# Arduino_Uno_v1_schematic.net
KiCad netlist of a schematic drawn in Altium Designer
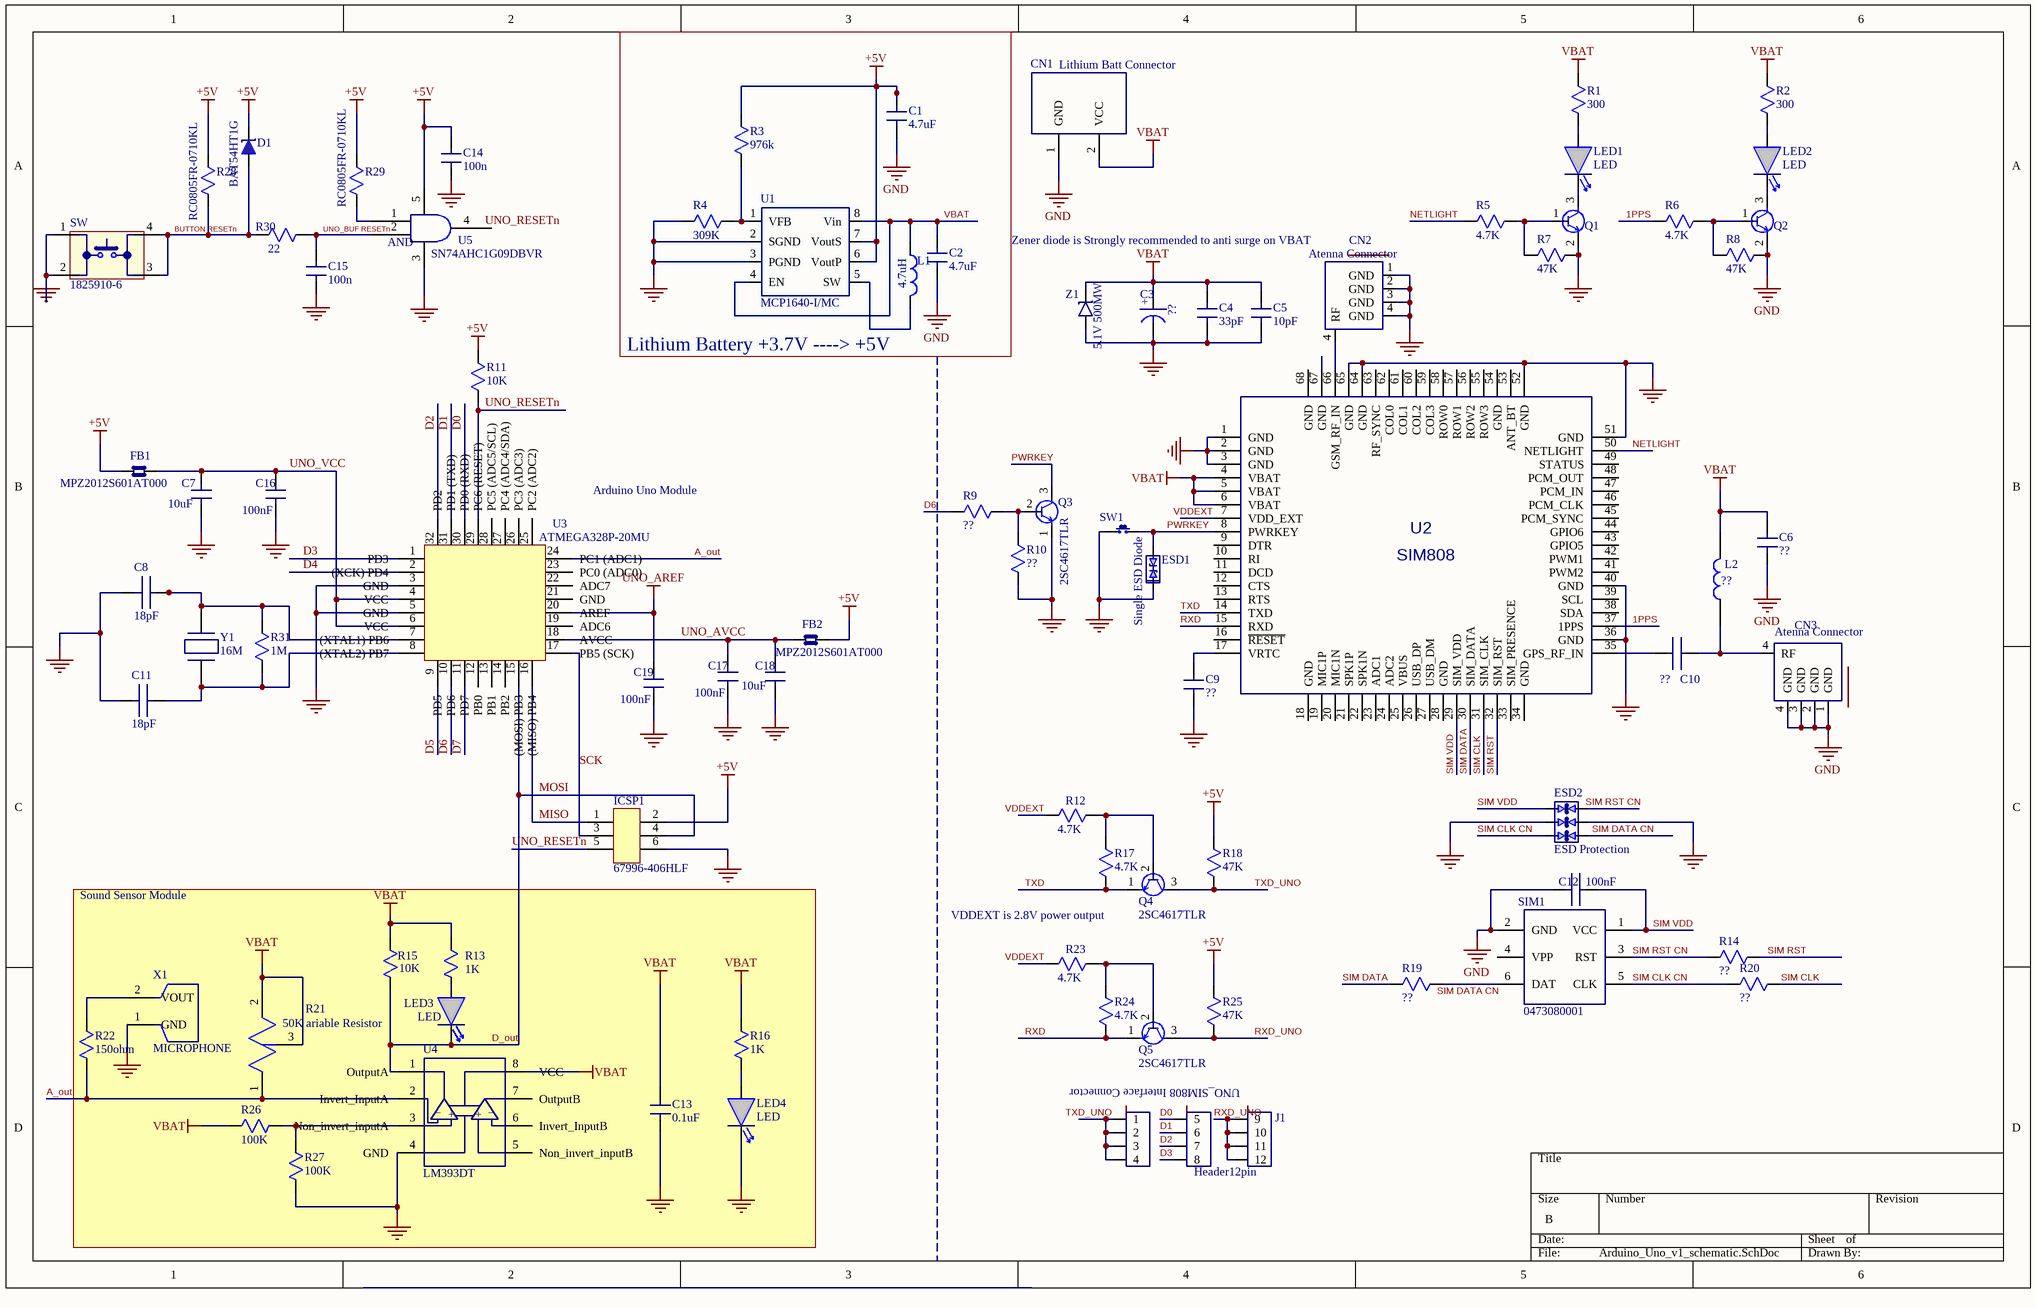
[diagram p0: Arduino_Uno_v1_schematic.SchDoc]

(export (version "E")
  (design (tool "Eeschema 10.0.6"))
  (components
    (comp (ref "C1")
      (value "4.7uF")
      (description "Capacitor")
      (libsource (lib "Arduino_Uno_v1") (part "Capacitor"))
    )
    (comp (ref "C2")
      (value "4.7uF")
      (description "Capacitor")
      (libsource (lib "Arduino_Uno_v1") (part "Capacitor"))
    )
    (comp (ref "C3")
      (value "??")
      (description "CAP NIOB OXI 4.7UF 20% 6.3V 1206")
      (fields
        (field (name "MANUFACTURER") "AVX Corporation")
        (field (name "MANUFACTURER PART NUMBER") "NOJA475M006RWJ")
      )
      (libsource (lib "Arduino_Uno_v1") (part "NOJA475M006RWJ"))
    )
    (comp (ref "C4")
      (value "33pF")
      (description "Capacitor")
      (libsource (lib "Arduino_Uno_v1") (part "Capacitor"))
    )
    (comp (ref "C5")
      (value "10pF")
      (description "Capacitor")
      (libsource (lib "Arduino_Uno_v1") (part "Capacitor"))
    )
    (comp (ref "C6")
      (value "??")
      (description "Capacitor")
      (libsource (lib "Arduino_Uno_v1") (part "Capacitor"))
    )
    (comp (ref "C7") (value "10uF") (description "Capacitor") (libsource (lib "") (part "Capacitor_1")))
    (comp (ref "C8")
      (value "18pF")
      (description "CAP CER 18PF 50V C0G/NP0 0805")
      (fields
        (field (name "MANUFACTURER") "KEMET")
        (field (name "MANUFACTURER PART NUMBER") "C0805C180J5GACTU")
      )
      (libsource (lib "Arduino_Uno_v1") (part "C0805C180J5GACTU"))
    )
    (comp (ref "C9") (value "??") (description "Capacitor") (libsource (lib "") (part "Capacitor_1")))
    (comp (ref "C10") (value "??") (description "Capacitor") (libsource (lib "") (part "Capacitor_2")))
    (comp (ref "C11")
      (value "18pF")
      (description "CAP CER 18PF 50V C0G/NP0 0805")
      (fields
        (field (name "MANUFACTURER") "KEMET")
        (field (name "MANUFACTURER PART NUMBER") "C0805C180J5GACTU")
      )
      (libsource (lib "Arduino_Uno_v1") (part "C0805C180J5GACTU"))
    )
    (comp (ref "C12") (value "100nF") (description "Capacitor") (libsource (lib "") (part "Capacitor_2")))
    (comp (ref "C13")
      (value "0.1uF")
      (description "Capacitor")
      (libsource (lib "Arduino_Uno_v1") (part "Capacitor"))
    )
    (comp (ref "C14")
      (value "100n")
      (description "Capacitor")
      (libsource (lib "Arduino_Uno_v1") (part "Capacitor"))
    )
    (comp (ref "C15")
      (value "100n")
      (description "Capacitor")
      (libsource (lib "Arduino_Uno_v1") (part "Capacitor"))
    )
    (comp (ref "C16") (value "100nF") (description "Capacitor") (libsource (lib "") (part "Capacitor_1")))
    (comp (ref "C17") (value "100nF") (description "Capacitor") (libsource (lib "") (part "Capacitor_1")))
    (comp (ref "C18") (value "10uF") (description "Capacitor") (libsource (lib "") (part "Capacitor_1")))
    (comp (ref "C19") (value "100nF") (description "Capacitor") (libsource (lib "") (part "Capacitor_1")))
    (comp (ref "CN1")
      (value "Lithium Batt Connector")
      (description "CONN HOUSING PH 2POS 2MM WHITE")
      (fields
        (field (name "MANUFACTURER") "JST Sales America Inc.")
        (field (name "MANUFACTURER PART NUMBER") "PHR-2")
      )
      (libsource (lib "Arduino_Uno_v1") (part "PHR-2"))
    )
    (comp (ref "CN2") (value "Atenna Connector") (libsource (lib "Arduino_Uno_v1") (part "Atenna Connector")))
    (comp (ref "CN3") (value "Atenna Connector") (libsource (lib "") (part "Atenna Connector_1")))
    (comp (ref "D1")
      (value "BAT54HT1G")
      (description "DIODE SCHOTTKY 30V 200MA SOD323")
      (fields (field (name "MANUFACTURER") "ON Semiconductor"))
      (libsource (lib "Arduino_Uno_v1") (part "BAT54HT1G"))
    )
    (comp (ref "ESD1")
      (value "Single ESD Diode")
      (description "TVS DIODE 7VWM/14VWM LLP10062L")
      (fields
        (field (name "MANUFACTURER") "Vishay Semiconductor Diodes Division")
        (field (name "MANUFACTURER PART NUMBER") "VCUT0714A-HD1-GS08")
      )
      (libsource (lib "Arduino_Uno_v1") (part "VCUT0714A-HD1-GS08"))
    )
    (comp (ref "ESD2")
      (value "ESD Protection")
      (description "TVS DIODE 12VWM UMD6")
      (fields
        (field (name "MANUFACTURER") "Rohm Semiconductor")
        (field (name "MANUFACTURER PART NUMBER") "RSB16X3NTR")
      )
      (libsource (lib "Arduino_Uno_v1") (part "RSB16X3NTR"))
    )
    (comp (ref "FB1")
      (value "MPZ2012S601AT000")
      (description "FERRITE BEAD 600 OHM 0805 1LN")
      (fields (field (name "MANUFACTURER") "TDK Corporation"))
      (libsource (lib "") (part "MPZ2012S601AT000_1"))
    )
    (comp (ref "FB2")
      (value "MPZ2012S601AT000")
      (description "FERRITE BEAD 600 OHM 0805 1LN")
      (fields (field (name "MANUFACTURER") "TDK Corporation"))
      (libsource (lib "Arduino_Uno_v1") (part "MPZ2012S601AT000"))
    )
    (comp (ref "ICSP1")
      (value "67996-406HLF")
      (description "CONN HEADER 6POS .100 STR TIN")
      (fields (field (name "MANUFACTURER") "Amphenol FCI"))
      (libsource (lib "Arduino_Uno_v1") (part "67996-406HLF"))
    )
    (comp (ref "J1")
      (value "Header12pin")
      (description "Software UART Jumper")
      (libsource (lib "Arduino_Uno_v1") (part "Header12pin"))
    )
    (comp (ref "L1")
      (value "4.7uH")
      (description "FERRITE BEAD 220 OHM 0805 1LN")
      (fields
        (field (name "MANUFACTURER") "Murata Electronics North America")
        (field (name "MANUFACTURER PART NUMBER") "BLM21PG221SN1D")
      )
      (libsource (lib "") (part "BLM21PG221SN1D_1"))
    )
    (comp (ref "L2")
      (value "??")
      (description "FERRITE BEAD 220 OHM 0805 1LN")
      (fields
        (field (name "MANUFACTURER") "Murata Electronics North America")
        (field (name "MANUFACTURER PART NUMBER") "BLM21PG221SN1D")
      )
      (libsource (lib "Arduino_Uno_v1") (part "BLM21PG221SN1D"))
    )
    (comp (ref "LED1") (value "LED") (libsource (lib "Arduino_Uno_v1") (part "LED")))
    (comp (ref "LED2") (value "LED") (libsource (lib "Arduino_Uno_v1") (part "LED")))
    (comp (ref "LED3") (value "LED") (libsource (lib "Arduino_Uno_v1") (part "LED")))
    (comp (ref "LED4") (value "LED") (libsource (lib "Arduino_Uno_v1") (part "LED")))
    (comp (ref "Q1")
      (value "TRANS NPN")
      (description "TRANS NPN 40V 0.6A SOT23")
      (fields
        (field (name "MANUFACTURER") "ON Semiconductor")
        (field (name "MANUFACTURER PART NUMBER") "MMBT2222ALT1G")
      )
      (libsource (lib "Arduino_Uno_v1") (part "MMBT2222ALT1G"))
    )
    (comp (ref "Q2")
      (value "TRANS NPN")
      (description "TRANS NPN 40V 0.6A SOT23")
      (fields
        (field (name "MANUFACTURER") "ON Semiconductor")
        (field (name "MANUFACTURER PART NUMBER") "MMBT2222ALT1G")
      )
      (libsource (lib "Arduino_Uno_v1") (part "MMBT2222ALT1G"))
    )
    (comp (ref "Q3")
      (value "2SC4617TLR")
      (description "TRANS NPN 50V 0.15A SOT-416")
      (fields (field (name "MANUFACTURER") "Rohm Semiconductor"))
      (libsource (lib "") (part "2SC4617TLR_1"))
    )
    (comp (ref "Q4")
      (value "2SC4617TLR")
      (description "TRANS NPN 50V 0.15A SOT-416")
      (fields (field (name "MANUFACTURER") "Rohm Semiconductor"))
      (libsource (lib "Arduino_Uno_v1") (part "2SC4617TLR"))
    )
    (comp (ref "Q5")
      (value "2SC4617TLR")
      (description "TRANS NPN 50V 0.15A SOT-416")
      (fields (field (name "MANUFACTURER") "Rohm Semiconductor"))
      (libsource (lib "Arduino_Uno_v1") (part "2SC4617TLR"))
    )
    (comp (ref "R1") (value "300") (libsource (lib "Arduino_Uno_v1") (part "Resistor")))
    (comp (ref "R2") (value "300") (libsource (lib "Arduino_Uno_v1") (part "Resistor")))
    (comp (ref "R3") (value "976k") (libsource (lib "Arduino_Uno_v1") (part "Resistor")))
    (comp (ref "R4") (value "309K") (libsource (lib "Arduino_Uno_v1") (part "Resistor")))
    (comp (ref "R5") (value "4.7K") (libsource (lib "Arduino_Uno_v1") (part "Resistor")))
    (comp (ref "R6") (value "4.7K") (libsource (lib "Arduino_Uno_v1") (part "Resistor")))
    (comp (ref "R7") (value "47K") (libsource (lib "Arduino_Uno_v1") (part "Resistor")))
    (comp (ref "R8") (value "47K") (libsource (lib "Arduino_Uno_v1") (part "Resistor")))
    (comp (ref "R9") (value "??") (libsource (lib "Arduino_Uno_v1") (part "Resistor")))
    (comp (ref "R10") (value "??") (libsource (lib "Arduino_Uno_v1") (part "Resistor")))
    (comp (ref "R11") (value "10K") (libsource (lib "Arduino_Uno_v1") (part "Resistor")))
    (comp (ref "R12") (value "4.7K") (libsource (lib "Arduino_Uno_v1") (part "Resistor")))
    (comp (ref "R13") (value "1K") (libsource (lib "Arduino_Uno_v1") (part "Resistor")))
    (comp (ref "R14") (value "??") (libsource (lib "Arduino_Uno_v1") (part "Resistor")))
    (comp (ref "R15") (value "10K") (libsource (lib "Arduino_Uno_v1") (part "Resistor")))
    (comp (ref "R16") (value "1K") (libsource (lib "Arduino_Uno_v1") (part "Resistor")))
    (comp (ref "R17") (value "4.7K") (libsource (lib "Arduino_Uno_v1") (part "Resistor")))
    (comp (ref "R18") (value "47K") (libsource (lib "Arduino_Uno_v1") (part "Resistor")))
    (comp (ref "R19") (value "??") (libsource (lib "Arduino_Uno_v1") (part "Resistor")))
    (comp (ref "R20") (value "??") (libsource (lib "Arduino_Uno_v1") (part "Resistor")))
    (comp (ref "R21")
      (value "50K ariable Resistor")
      (description "POT 10K OHM 1/20W PLASTIC LINEAR")
      (fields
        (field (name "MANUFACTURER") "TT Electronics/BI")
        (field (name "MANUFACTURER PART NUMBER") "P0915N-FC15BR10K")
      )
      (libsource (lib "Arduino_Uno_v1") (part "P0915N-FC15BR10K"))
    )
    (comp (ref "R22") (value "150ohm") (libsource (lib "Arduino_Uno_v1") (part "Resistor")))
    (comp (ref "R23") (value "4.7K") (libsource (lib "Arduino_Uno_v1") (part "Resistor")))
    (comp (ref "R24") (value "4.7K") (libsource (lib "Arduino_Uno_v1") (part "Resistor")))
    (comp (ref "R25") (value "47K") (libsource (lib "Arduino_Uno_v1") (part "Resistor")))
    (comp (ref "R26") (value "100K") (libsource (lib "Arduino_Uno_v1") (part "Resistor")))
    (comp (ref "R27") (value "100K") (libsource (lib "Arduino_Uno_v1") (part "Resistor")))
    (comp (ref "R28")
      (value "RC0805FR-0710KL")
      (description "RES SMD 10K OHM 1% 1/8W 0805")
      (fields (field (name "MANUFACTURER") "Yageo") (field (name "TOLERANCE") "±1%"))
      (libsource (lib "Arduino_Uno_v1") (part "RC0805FR-0710KL"))
    )
    (comp (ref "R29")
      (value "RC0805FR-0710KL")
      (description "RES SMD 10K OHM 1% 1/8W 0805")
      (fields (field (name "MANUFACTURER") "Yageo") (field (name "TOLERANCE") "±1%"))
      (libsource (lib "Arduino_Uno_v1") (part "RC0805FR-0710KL"))
    )
    (comp (ref "R30") (value "22") (libsource (lib "Arduino_Uno_v1") (part "Resistor")))
    (comp (ref "R31")
      (value "1M")
      (description "RES SMD 1M OHM 1% 1/8W 0805")
      (fields
        (field (name "MANUFACTURER") "Yageo")
        (field (name "MANUFACTURER PART NUMBER") "RC0805FR-071ML")
      )
      (libsource (lib "Arduino_Uno_v1") (part "RC0805FR-071ML"))
    )
    (comp (ref "SIM1")
      (value "0473080001")
      (description "CONN SIM CARD PUSH-PULL R/A SMD")
      (fields (field (name "MANUFACTURER") "Molex, LLC"))
      (libsource (lib "Arduino_Uno_v1") (part "0473080001"))
    )
    (comp (ref "SW")
      (value "1825910-6")
      (description "SWITCH TACTILE SPST-NO 0.05A 24V")
      (fields (field (name "MANUFACTURER") "TE Connectivity ALCOSWITCH Switches"))
      (libsource (lib "Arduino_Uno_v1") (part "1825910-6"))
    )
    (comp (ref "SW1") (value "SWITCH") (libsource (lib "Arduino_Uno_v1") (part "SWITCH")))
    (comp (ref "U1")
      (value "MCP1640-I/MC")
      (description "IC REG BOOST ADJ 0.35A SYNC 8DFN")
      (fields (field (name "MANUFACTURER") "Microchip Technology"))
      (libsource (lib "Arduino_Uno_v1") (part "MCP1640-I/MC"))
    )
    (comp (ref "U2")
      (value "SIM808")
      (footprint "QFN100P2400X2400X260-68N")
      (description "Module: GPS/GSM; GPRS; 2G; 1800MHz, 900MHz; GPIO, Serial, USB; SMD")
      (fields (field (name "MF") "Simcom"))
      (libsource (lib "Arduino_Uno_v1") (part "SIM808"))
    )
    (comp (ref "U3")
      (value "ATMEGA328P-20MU")
      (description "IC MCU 8BIT 32KB FLASH 32SMD")
      (fields
        (field (name "MANUFACTURER") "Microchip Technology")
        (field (name "MANUFACTURER PART NUMBER") "ATMEGA328P-PU")
      )
      (libsource (lib "Arduino_Uno_v1") (part "ATMEGA328P-20MU"))
    )
    (comp (ref "U4")
      (value "LM393DT")
      (description "IC COMPARATOR LP DUAL 8-SOIC")
      (fields (field (name "MANUFACTURER") "STMicroelectronics"))
      (libsource (lib "Arduino_Uno_v1") (part "LM393DT"))
    )
    (comp (ref "U5")
      (value "SN74AHC1G09DBVR")
      (description "IC GATE AND 1CH 2-INP SOT-23-5")
      (fields (field (name "MANUFACTURER") "Texas Instruments"))
      (libsource (lib "Arduino_Uno_v1") (part "SN74AHC1G09DBVR"))
    )
    (comp (ref "X1")
      (value "MICROPHONE")
      (description "MIC COND ANALOG OMNI -44DB")
      (fields
        (field (name "MANUFACTURER") "CUI Inc.")
        (field (name "MANUFACTURER PART NUMBER") "CMA-4544PF-W")
      )
      (libsource (lib "Arduino_Uno_v1") (part "CMA-4544PF-W"))
    )
    (comp (ref "Y1")
      (value "16M")
      (description "OSC MEMS 16.000MHZ CMOS SMD")
      (fields
        (field (name "MANUFACTURER") "Abracon LLC")
        (field (name "MANUFACTURER PART NUMBER") "ASDM1-16.000MHZ-LC-T")
      )
      (libsource (lib "Arduino_Uno_v1") (part "ASDM1-16.000MHZ-LC-T"))
    )
    (comp (ref "Z1")
      (value "5.1V 500MW")
      (description "DIODE ZENER 500MW 5.1V SOD123")
      (fields
        (field (name "MANUFACTURER") "ON Semiconductor")
        (field (name "MANUFACTURER PART NUMBER") "SZMMSZ5231BT1G")
      )
      (libsource (lib "Arduino_Uno_v1") (part "SZMMSZ5231BT1G"))
    )
  )
  (nets
    (net (code "1") (name "+5V") (class "Default")
      (node (ref "C1") (pin "2") (pinfunction "2_2") (pintype "passive"))
      (node (ref "C14") (pin "2") (pinfunction "2_2") (pintype "passive"))
      (node (ref "D1") (pin "1") (pinfunction "Cathode_1") (pintype "passive"))
      (node (ref "FB1") (pin "1") (pinfunction "1_1") (pintype "passive"))
      (node (ref "FB2") (pin "1") (pinfunction "1_1") (pintype "passive"))
      (node (ref "ICSP1") (pin "2") (pinfunction "2_2") (pintype "passive"))
      (node (ref "R11") (pin "1") (pinfunction "1_1") (pintype "passive"))
      (node (ref "R18") (pin "2") (pinfunction "2_2") (pintype "passive"))
      (node (ref "R25") (pin "2") (pinfunction "2_2") (pintype "passive"))
      (node (ref "R28") (pin "2") (pinfunction "2_2") (pintype "passive"))
      (node (ref "R29") (pin "2") (pinfunction "2_2") (pintype "passive"))
      (node (ref "R3") (pin "2") (pinfunction "2_2") (pintype "passive"))
      (node (ref "U1") (pin "6") (pinfunction "VoutP_6") (pintype "passive"))
      (node (ref "U1") (pin "7") (pinfunction "VoutS_7") (pintype "passive"))
      (node (ref "U5") (pin "5") (pinfunction "5_5") (pintype "passive"))
    )
    (net (code "2") (name "/1PPS") (class "Default")
      (node (ref "R6") (pin "1") (pinfunction "1_1") (pintype "passive"))
      (node (ref "U2") (pin "37") (pinfunction "1PPS_37") (pintype "passive"))
    )
    (net (code "3") (name "/A_out") (class "Default")
      (node (ref "R21") (pin "1") (pinfunction "1_1") (pintype "passive"))
      (node (ref "R22") (pin "2") (pinfunction "2_2") (pintype "passive"))
    )
    (net (code "4") (name "/BUTTON RESETn") (class "Default")
      (node (ref "D1") (pin "2") (pinfunction "Anode_2") (pintype "passive"))
      (node (ref "R28") (pin "1") (pinfunction "1_1") (pintype "passive"))
      (node (ref "R30") (pin "1") (pinfunction "1_1") (pintype "passive"))
      (node (ref "SW") (pin "3") (pinfunction "3_3") (pintype "passive"))
      (node (ref "SW") (pin "4") (pinfunction "4_4") (pintype "passive"))
    )
    (net (code "5") (name "/D0") (class "Default")
      (node (ref "J1") (pin "5") (pinfunction "5_5") (pintype "passive"))
    )
    (net (code "6") (name "/D1") (class "Default")
      (node (ref "J1") (pin "6") (pinfunction "6_6") (pintype "passive"))
    )
    (net (code "7") (name "/D2") (class "Default")
      (node (ref "J1") (pin "7") (pinfunction "7_7") (pintype "passive"))
    )
    (net (code "8") (name "/D3") (class "Default")
      (node (ref "J1") (pin "8") (pinfunction "8_8") (pintype "passive"))
    )
    (net (code "11") (name "/D6") (class "Default")
      (node (ref "R9") (pin "2") (pinfunction "2_2") (pintype "passive"))
    )
    (net (code "13") (name "/D_out") (class "Default")
      (node (ref "ICSP1") (pin "4") (pinfunction "4_4") (pintype "passive"))
      (node (ref "LED3") (pin "2") (pinfunction "2_2") (pintype "passive"))
      (node (ref "R15") (pin "2") (pinfunction "2_2") (pintype "passive"))
    )
    (net (code "14") (name "/MISO") (class "Default")
      (node (ref "ICSP1") (pin "1") (pinfunction "MISO_1") (pintype "passive"))
    )
    (net (code "15") (name "/NETLIGHT") (class "Default")
      (node (ref "R5") (pin "1") (pinfunction "1_1") (pintype "passive"))
      (node (ref "U2") (pin "50") (pinfunction "NETLIGHT_50") (pintype "passive"))
    )
    (net (code "16") (name "/PWRKEY") (class "Default")
      (node (ref "ESD1") (pin "2") (pinfunction "2_2") (pintype "passive"))
      (node (ref "Q3") (pin "3") (pinfunction "3_3") (pintype "passive"))
      (node (ref "SW1") (pin "1") (pinfunction "1_1") (pintype "passive"))
      (node (ref "U2") (pin "8") (pinfunction "PWRKEY_8") (pintype "passive"))
    )
    (net (code "17") (name "/RXD") (class "Default")
      (node (ref "Q5") (pin "1") (pinfunction "1_1") (pintype "passive"))
      (node (ref "R24") (pin "1") (pinfunction "1_1") (pintype "passive"))
      (node (ref "U2") (pin "15") (pinfunction "RXD_15") (pintype "passive"))
    )
    (net (code "18") (name "/RXD_UNO") (class "Default")
      (node (ref "J1") (pin "10") (pinfunction "10_10") (pintype "passive"))
      (node (ref "J1") (pin "11") (pinfunction "11_11") (pintype "passive"))
      (node (ref "J1") (pin "12") (pinfunction "12_12") (pintype "passive"))
      (node (ref "J1") (pin "9") (pinfunction "9_9") (pintype "passive"))
      (node (ref "Q5") (pin "3") (pinfunction "3_3") (pintype "passive"))
      (node (ref "R25") (pin "1") (pinfunction "1_1") (pintype "passive"))
    )
    (net (code "19") (name "/SCK") (class "Default")
      (node (ref "ICSP1") (pin "3") (pinfunction "3_3") (pintype "passive"))
    )
    (net (code "20") (name "/SIM CLK") (class "Default")
      (node (ref "R20") (pin "1") (pinfunction "1_1") (pintype "passive"))
      (node (ref "U2") (pin "31") (pinfunction "SIM_CLK_31") (pintype "passive"))
    )
    (net (code "21") (name "/SIM CLK CN") (class "Default")
      (node (ref "ESD2") (pin "6") (pinfunction "6_6") (pintype "passive"))
      (node (ref "R20") (pin "2") (pinfunction "2_2") (pintype "passive"))
      (node (ref "SIM1") (pin "5") (pinfunction "CLK_5") (pintype "passive"))
    )
    (net (code "22") (name "/SIM DATA") (class "Default")
      (node (ref "R19") (pin "2") (pinfunction "2_2") (pintype "passive"))
      (node (ref "U2") (pin "30") (pinfunction "SIM_DATA_30") (pintype "passive"))
    )
    (net (code "23") (name "/SIM DATA CN") (class "Default")
      (node (ref "ESD2") (pin "1") (pinfunction "1_1") (pintype "passive"))
    )
    (net (code "24") (name "/SIM RST") (class "Default")
      (node (ref "R14") (pin "1") (pinfunction "1_1") (pintype "passive"))
      (node (ref "U2") (pin "32") (pinfunction "SIM_RST_32") (pintype "passive"))
    )
    (net (code "25") (name "/SIM RST CN") (class "Default")
      (node (ref "R14") (pin "2") (pinfunction "2_2") (pintype "passive"))
      (node (ref "SIM1") (pin "3") (pinfunction "RST_3") (pintype "passive"))
    )
    (net (code "26") (name "/SIM VDD") (class "Default")
      (node (ref "C12") (pin "2") (pinfunction "2_2") (pintype "passive"))
      (node (ref "ESD2") (pin "4") (pinfunction "4_4") (pintype "passive"))
      (node (ref "SIM1") (pin "1") (pinfunction "VCC_1") (pintype "passive"))
      (node (ref "U2") (pin "29") (pinfunction "SIM_VDD_29") (pintype "passive"))
    )
    (net (code "27") (name "/TXD") (class "Default")
      (node (ref "Q4") (pin "1") (pinfunction "1_1") (pintype "passive"))
      (node (ref "R17") (pin "1") (pinfunction "1_1") (pintype "passive"))
      (node (ref "U2") (pin "14") (pinfunction "TXD_14") (pintype "passive"))
    )
    (net (code "28") (name "/TXD_UNO") (class "Default")
      (node (ref "Q4") (pin "3") (pinfunction "3_3") (pintype "passive"))
      (node (ref "R18") (pin "1") (pinfunction "1_1") (pintype "passive"))
    )
    (net (code "29") (name "/UNO_AVCC") (class "Default")
      (node (ref "C17") (pin "1") (pinfunction "1_1") (pintype "passive"))
      (node (ref "C18") (pin "1") (pinfunction "1_1") (pintype "passive"))
      (node (ref "FB2") (pin "2") (pinfunction "2_2") (pintype "passive"))
    )
    (net (code "30") (name "/UNO_BUF RESETn") (class "Default")
      (node (ref "C15") (pin "2") (pinfunction "2_2") (pintype "passive"))
      (node (ref "R30") (pin "2") (pinfunction "2_2") (pintype "passive"))
      (node (ref "U5") (pin "2") (pinfunction "2_2") (pintype "passive"))
    )
    (net (code "31") (name "/UNO_RESETn") (class "Default")
      (node (ref "ICSP1") (pin "5") (pinfunction "5_5") (pintype "passive"))
      (node (ref "R11") (pin "2") (pinfunction "2_2") (pintype "passive"))
    )
    (net (code "32") (name "/UNO_VCC") (class "Default")
      (node (ref "C16") (pin "1") (pinfunction "1_1") (pintype "passive"))
      (node (ref "C7") (pin "1") (pinfunction "1_1") (pintype "passive"))
      (node (ref "FB1") (pin "2") (pinfunction "2_2") (pintype "passive"))
    )
    (net (code "34") (name "GND") (class "Default")
      (node (ref "C1") (pin "1") (pinfunction "1_1") (pintype "passive"))
      (node (ref "C11") (pin "1") (pinfunction "1_1") (pintype "passive"))
      (node (ref "C12") (pin "1") (pinfunction "1_1") (pintype "passive"))
      (node (ref "C13") (pin "1") (pinfunction "1_1") (pintype "passive"))
      (node (ref "C14") (pin "1") (pinfunction "1_1") (pintype "passive"))
      (node (ref "C15") (pin "1") (pinfunction "1_1") (pintype "passive"))
      (node (ref "C16") (pin "2") (pinfunction "2_2") (pintype "passive"))
      (node (ref "C17") (pin "2") (pinfunction "2_2") (pintype "passive"))
      (node (ref "C18") (pin "2") (pinfunction "2_2") (pintype "passive"))
      (node (ref "C19") (pin "2") (pinfunction "2_2") (pintype "passive"))
      (node (ref "C2") (pin "1") (pinfunction "1_1") (pintype "passive"))
      (node (ref "C3") (pin "1") (pinfunction "1_1") (pintype "passive"))
      (node (ref "C4") (pin "1") (pinfunction "1_1") (pintype "passive"))
      (node (ref "C5") (pin "1") (pinfunction "1_1") (pintype "passive"))
      (node (ref "C6") (pin "1") (pinfunction "1_1") (pintype "passive"))
      (node (ref "C7") (pin "2") (pinfunction "2_2") (pintype "passive"))
      (node (ref "C8") (pin "1") (pinfunction "1_1") (pintype "passive"))
      (node (ref "C9") (pin "2") (pinfunction "2_2") (pintype "passive"))
      (node (ref "CN1") (pin "1") (pinfunction "GND_1") (pintype "passive"))
      (node (ref "CN2") (pin "1") (pinfunction "GND_1") (pintype "passive"))
      (node (ref "CN2") (pin "2") (pinfunction "GND_2") (pintype "passive"))
      (node (ref "CN2") (pin "3") (pinfunction "GND_3") (pintype "passive"))
      (node (ref "CN2") (pin "4") (pinfunction "GND_4") (pintype "passive"))
      (node (ref "CN3") (pin "1") (pinfunction "GND_1") (pintype "passive"))
      (node (ref "CN3") (pin "2") (pinfunction "GND_2") (pintype "passive"))
      (node (ref "CN3") (pin "3") (pinfunction "GND_3") (pintype "passive"))
      (node (ref "CN3") (pin "4") (pinfunction "GND_4") (pintype "passive"))
      (node (ref "ESD1") (pin "1") (pinfunction "1_1") (pintype "passive"))
      (node (ref "ESD2") (pin "2") (pinfunction "2_2") (pintype "passive"))
      (node (ref "ESD2") (pin "5") (pinfunction "5_5") (pintype "passive"))
      (node (ref "ICSP1") (pin "6") (pinfunction "6_6") (pintype "passive"))
      (node (ref "LED4") (pin "2") (pinfunction "2_2") (pintype "passive"))
      (node (ref "Q1") (pin "2") (pinfunction "2_2") (pintype "passive"))
      (node (ref "Q2") (pin "2") (pinfunction "2_2") (pintype "passive"))
      (node (ref "Q3") (pin "1") (pinfunction "1_1") (pintype "passive"))
      (node (ref "R10") (pin "2") (pinfunction "2_2") (pintype "passive"))
      (node (ref "R27") (pin "2") (pinfunction "2_2") (pintype "passive"))
      (node (ref "R4") (pin "1") (pinfunction "1_1") (pintype "passive"))
      (node (ref "R7") (pin "2") (pinfunction "2_2") (pintype "passive"))
      (node (ref "R8") (pin "2") (pinfunction "2_2") (pintype "passive"))
      (node (ref "SIM1") (pin "2") (pinfunction "GND_2") (pintype "passive"))
      (node (ref "SW") (pin "1") (pinfunction "1_1") (pintype "passive"))
      (node (ref "SW") (pin "2") (pinfunction "2_2") (pintype "passive"))
      (node (ref "SW1") (pin "1") (pinfunction "1_1") (pintype "passive"))
      (node (ref "U1") (pin "2") (pinfunction "SGND_2") (pintype "passive"))
      (node (ref "U1") (pin "3") (pinfunction "PGND_3") (pintype "passive"))
      (node (ref "U2") (pin "1") (pinfunction "GND_1") (pintype "passive"))
      (node (ref "U2") (pin "2") (pinfunction "GND_2") (pintype "passive"))
      (node (ref "U2") (pin "3") (pinfunction "GND_3") (pintype "passive"))
      (node (ref "U2") (pin "36") (pinfunction "GND_36") (pintype "passive"))
      (node (ref "U2") (pin "40") (pinfunction "GND_40") (pintype "passive"))
      (node (ref "U2") (pin "51") (pinfunction "GND_51") (pintype "passive"))
      (node (ref "U2") (pin "52") (pinfunction "GND_52") (pintype "passive"))
      (node (ref "U2") (pin "64") (pinfunction "GND_64") (pintype "passive"))
      (node (ref "U2") (pin "65") (pinfunction "GND_65") (pintype "passive"))
      (node (ref "U5") (pin "3") (pinfunction "3_3") (pintype "passive"))
      (node (ref "X1") (pin "1") (pinfunction "GND_1") (pintype "passive"))
      (node (ref "Z1") (pin "1") (pinfunction "1_1") (pintype "passive"))
    )
    (net (code "35") (name "Net-(C8-Pad2)") (class "Default")
      (node (ref "C8") (pin "2") (pinfunction "2_2") (pintype "passive"))
      (node (ref "R31") (pin "2") (pinfunction "2_2") (pintype "passive"))
      (node (ref "Y1") (pin "1") (pinfunction "1_1") (pintype "passive"))
    )
    (net (code "36") (name "Net-(C11-Pad2)") (class "Default")
      (node (ref "C11") (pin "2") (pinfunction "2_2") (pintype "passive"))
      (node (ref "R31") (pin "1") (pinfunction "1_1") (pintype "passive"))
      (node (ref "Y1") (pin "2") (pinfunction "2_2") (pintype "passive"))
    )
    (net (code "37") (name "Net-(CN2-RF)") (class "Default")
      (node (ref "CN2") (pin "4") (pinfunction "RF_4") (pintype "passive"))
      (node (ref "U2") (pin "66") (pinfunction "GSM_RF_IN_66") (pintype "passive"))
    )
    (net (code "38") (name "Net-(CN3-RF)") (class "Default")
      (node (ref "C10") (pin "2") (pinfunction "2_2") (pintype "passive"))
      (node (ref "CN3") (pin "4") (pinfunction "RF_4") (pintype "passive"))
      (node (ref "L2") (pin "1") (pinfunction "1_1") (pintype "passive"))
    )
    (net (code "39") (name "Net-(J1-Pad1)") (class "Default")
      (node (ref "J1") (pin "1") (pinfunction "1_1") (pintype "passive"))
      (node (ref "J1") (pin "2") (pinfunction "2_2") (pintype "passive"))
      (node (ref "J1") (pin "3") (pinfunction "3_3") (pintype "passive"))
      (node (ref "J1") (pin "4") (pinfunction "4_4") (pintype "passive"))
    )
    (net (code "40") (name "Net-(LED1-Pad1)") (class "Default")
      (node (ref "LED1") (pin "1") (pinfunction "1_1") (pintype "passive"))
      (node (ref "R1") (pin "1") (pinfunction "1_1") (pintype "passive"))
    )
    (net (code "41") (name "Net-(LED1-Pad2)") (class "Default")
      (node (ref "LED1") (pin "2") (pinfunction "2_2") (pintype "passive"))
      (node (ref "Q1") (pin "3") (pinfunction "3_3") (pintype "passive"))
    )
    (net (code "42") (name "Net-(LED2-Pad1)") (class "Default")
      (node (ref "LED2") (pin "1") (pinfunction "1_1") (pintype "passive"))
      (node (ref "R2") (pin "1") (pinfunction "1_1") (pintype "passive"))
    )
    (net (code "43") (name "Net-(LED2-Pad2)") (class "Default")
      (node (ref "LED2") (pin "2") (pinfunction "2_2") (pintype "passive"))
      (node (ref "Q2") (pin "3") (pinfunction "3_3") (pintype "passive"))
    )
    (net (code "44") (name "Net-(LED3-Pad1)") (class "Default")
      (node (ref "LED3") (pin "1") (pinfunction "1_1") (pintype "passive"))
      (node (ref "R13") (pin "2") (pinfunction "2_2") (pintype "passive"))
    )
    (net (code "45") (name "Net-(LED4-Pad1)") (class "Default")
      (node (ref "LED4") (pin "1") (pinfunction "1_1") (pintype "passive"))
      (node (ref "R16") (pin "2") (pinfunction "2_2") (pintype "passive"))
    )
    (net (code "46") (name "Net-(Q1-Pad1)") (class "Default")
      (node (ref "Q1") (pin "1") (pinfunction "1_1") (pintype "passive"))
      (node (ref "R5") (pin "2") (pinfunction "2_2") (pintype "passive"))
      (node (ref "R7") (pin "1") (pinfunction "1_1") (pintype "passive"))
    )
    (net (code "47") (name "Net-(Q2-Pad1)") (class "Default")
      (node (ref "Q2") (pin "1") (pinfunction "1_1") (pintype "passive"))
      (node (ref "R6") (pin "2") (pinfunction "2_2") (pintype "passive"))
      (node (ref "R8") (pin "1") (pinfunction "1_1") (pintype "passive"))
    )
    (net (code "48") (name "Net-(Q3-Pad2)") (class "Default")
      (node (ref "Q3") (pin "2") (pinfunction "2_2") (pintype "passive"))
      (node (ref "R10") (pin "1") (pinfunction "1_1") (pintype "passive"))
      (node (ref "R9") (pin "1") (pinfunction "1_1") (pintype "passive"))
    )
    (net (code "49") (name "Net-(Q4-Pad2)") (class "Default")
      (node (ref "Q4") (pin "2") (pinfunction "2_2") (pintype "passive"))
      (node (ref "R12") (pin "1") (pinfunction "1_1") (pintype "passive"))
      (node (ref "R17") (pin "2") (pinfunction "2_2") (pintype "passive"))
    )
    (net (code "50") (name "Net-(Q5-Pad2)") (class "Default")
      (node (ref "Q5") (pin "2") (pinfunction "2_2") (pintype "passive"))
      (node (ref "R23") (pin "1") (pinfunction "1_1") (pintype "passive"))
      (node (ref "R24") (pin "2") (pinfunction "2_2") (pintype "passive"))
    )
    (net (code "51") (name "Net-(R26-Pad2)") (class "Default")
      (node (ref "R26") (pin "2") (pinfunction "2_2") (pintype "passive"))
      (node (ref "R27") (pin "1") (pinfunction "1_1") (pintype "passive"))
    )
    (net (code "52") (name "Net-(R29-Pad1)") (class "Default")
      (node (ref "R29") (pin "1") (pinfunction "1_1") (pintype "passive"))
      (node (ref "U5") (pin "1") (pinfunction "1_1") (pintype "passive"))
    )
    (net (code "53") (name "Net-(SIM1-DAT)") (class "Default")
      (node (ref "R19") (pin "1") (pinfunction "1_1") (pintype "passive"))
      (node (ref "SIM1") (pin "6") (pinfunction "DAT_6") (pintype "passive"))
    )
    (net (code "54") (name "Net-(U1-SW)") (class "Default")
      (node (ref "L1") (pin "2") (pinfunction "2_2") (pintype "passive"))
      (node (ref "U1") (pin "5") (pinfunction "SW_5") (pintype "passive"))
    )
    (net (code "55") (name "Net-(U1-VFB)") (class "Default")
      (node (ref "R3") (pin "1") (pinfunction "1_1") (pintype "passive"))
      (node (ref "R4") (pin "2") (pinfunction "2_2") (pintype "passive"))
      (node (ref "U1") (pin "1") (pinfunction "VFB_1") (pintype "passive"))
    )
    (net (code "56") (name "Net-(U2-GPS_RF_IN)") (class "Default")
      (node (ref "C10") (pin "1") (pinfunction "1_1") (pintype "passive"))
      (node (ref "U2") (pin "35") (pinfunction "GPS_RF_IN_35") (pintype "passive"))
    )
    (net (code "57") (name "Net-(U2-VRTC)") (class "Default")
      (node (ref "C9") (pin "1") (pinfunction "1_1") (pintype "passive"))
      (node (ref "U2") (pin "17") (pinfunction "VRTC_17") (pintype "power_in"))
    )
    (net (code "58") (name "Net-(X1-VOUT)") (class "Default")
      (node (ref "R22") (pin "1") (pinfunction "1_1") (pintype "passive"))
      (node (ref "X1") (pin "2") (pinfunction "VOUT_2") (pintype "passive"))
    )
    (net (code "59") (name "UNO_AREF") (class "Default")
      (node (ref "C19") (pin "1") (pinfunction "1_1") (pintype "passive"))
    )
    (net (code "60") (name "VBAT") (class "Default")
      (node (ref "C13") (pin "2") (pinfunction "2_2") (pintype "passive"))
      (node (ref "C2") (pin "2") (pinfunction "2_2") (pintype "passive"))
      (node (ref "C3") (pin "2") (pinfunction "2_2") (pintype "passive"))
      (node (ref "C4") (pin "2") (pinfunction "2_2") (pintype "passive"))
      (node (ref "C5") (pin "2") (pinfunction "2_2") (pintype "passive"))
      (node (ref "C6") (pin "2") (pinfunction "2_2") (pintype "passive"))
      (node (ref "CN1") (pin "2") (pinfunction "VCC_2") (pintype "passive"))
      (node (ref "L1") (pin "1") (pinfunction "1_1") (pintype "passive"))
      (node (ref "L2") (pin "1") (pinfunction "1_1") (pintype "passive"))
      (node (ref "R1") (pin "2") (pinfunction "2_2") (pintype "passive"))
      (node (ref "R13") (pin "1") (pinfunction "1_1") (pintype "passive"))
      (node (ref "R15") (pin "1") (pinfunction "1_1") (pintype "passive"))
      (node (ref "R16") (pin "1") (pinfunction "1_1") (pintype "passive"))
      (node (ref "R2") (pin "2") (pinfunction "2_2") (pintype "passive"))
      (node (ref "R21") (pin "2") (pinfunction "2_2") (pintype "passive"))
      (node (ref "R21") (pin "3") (pinfunction "3_3") (pintype "passive"))
      (node (ref "R26") (pin "1") (pinfunction "1_1") (pintype "passive"))
      (node (ref "U1") (pin "4") (pinfunction "EN_4") (pintype "passive"))
      (node (ref "U1") (pin "8") (pinfunction "Vin_8") (pintype "passive"))
      (node (ref "U2") (pin "4") (pinfunction "VBAT_4") (pintype "power_in"))
      (node (ref "U2") (pin "5") (pinfunction "VBAT_5") (pintype "power_in"))
      (node (ref "U2") (pin "6") (pinfunction "VBAT_6") (pintype "power_in"))
      (node (ref "Z1") (pin "1") (pinfunction "1_1") (pintype "passive"))
    )
    (net (code "61") (name "unconnected-(ESD2-Pad3)") (class "Default")
      (node (ref "ESD2") (pin "3") (pinfunction "3_3") (pintype "passive"))
    )
    (net (code "62") (name "unconnected-(R12-Pad2)") (class "Default")
      (node (ref "R12") (pin "2") (pinfunction "2_2") (pintype "passive"))
    )
    (net (code "63") (name "unconnected-(R23-Pad2)") (class "Default")
      (node (ref "R23") (pin "2") (pinfunction "2_2") (pintype "passive"))
    )
    (net (code "64") (name "unconnected-(SIM1-VPP-Pad4)") (class "Default")
      (node (ref "SIM1") (pin "4") (pinfunction "VPP_4") (pintype "passive"))
    )
    (net (code "65") (name "unconnected-(U2-ADC1-Pad23)") (class "Default")
      (node (ref "U2") (pin "23") (pinfunction "ADC1_23") (pintype "passive"))
    )
    (net (code "66") (name "unconnected-(U2-ADC2-Pad24)") (class "Default")
      (node (ref "U2") (pin "24") (pinfunction "ADC2_24") (pintype "passive"))
    )
    (net (code "67") (name "unconnected-(U2-ANT_BT-Pad53)") (class "Default")
      (node (ref "U2") (pin "53") (pinfunction "ANT_BT_53") (pintype "passive"))
    )
    (net (code "68") (name "unconnected-(U2-COL0-Pad62)") (class "Default")
      (node (ref "U2") (pin "62") (pinfunction "COL0_62") (pintype "passive"))
    )
    (net (code "69") (name "unconnected-(U2-COL1-Pad61)") (class "Default")
      (node (ref "U2") (pin "61") (pinfunction "COL1_61") (pintype "passive"))
    )
    (net (code "70") (name "unconnected-(U2-COL2-Pad60)") (class "Default")
      (node (ref "U2") (pin "60") (pinfunction "COL2_60") (pintype "passive"))
    )
    (net (code "71") (name "unconnected-(U2-COL3-Pad59)") (class "Default")
      (node (ref "U2") (pin "59") (pinfunction "COL3_59") (pintype "passive"))
    )
    (net (code "72") (name "unconnected-(U2-CTS-Pad12)") (class "Default")
      (node (ref "U2") (pin "12") (pinfunction "CTS_12") (pintype "passive"))
    )
    (net (code "73") (name "unconnected-(U2-DCD-Pad11)") (class "Default")
      (node (ref "U2") (pin "11") (pinfunction "DCD_11") (pintype "passive"))
    )
    (net (code "74") (name "unconnected-(U2-DTR-Pad9)") (class "Default")
      (node (ref "U2") (pin "9") (pinfunction "DTR_9") (pintype "passive"))
    )
    (net (code "75") (name "unconnected-(U2-GND-Pad18)") (class "Default")
      (node (ref "U2") (pin "18") (pinfunction "GND_18") (pintype "passive"))
    )
    (net (code "76") (name "unconnected-(U2-GND-Pad28)") (class "Default")
      (node (ref "U2") (pin "28") (pinfunction "GND_28") (pintype "passive"))
    )
    (net (code "77") (name "unconnected-(U2-GND-Pad34)") (class "Default")
      (node (ref "U2") (pin "34") (pinfunction "GND_34") (pintype "passive"))
    )
    (net (code "78") (name "unconnected-(U2-GND-Pad54)") (class "Default")
      (node (ref "U2") (pin "54") (pinfunction "GND_54") (pintype "passive"))
    )
    (net (code "79") (name "unconnected-(U2-GND-Pad67)") (class "Default")
      (node (ref "U2") (pin "67") (pinfunction "GND_67") (pintype "passive"))
    )
    (net (code "80") (name "unconnected-(U2-GND-Pad68)") (class "Default")
      (node (ref "U2") (pin "68") (pinfunction "GND_68") (pintype "passive"))
    )
    (net (code "81") (name "unconnected-(U2-GPIO5-Pad43)") (class "Default")
      (node (ref "U2") (pin "43") (pinfunction "GPIO5_43") (pintype "passive"))
    )
    (net (code "82") (name "unconnected-(U2-GPIO6-Pad44)") (class "Default")
      (node (ref "U2") (pin "44") (pinfunction "GPIO6_44") (pintype "passive"))
    )
    (net (code "83") (name "unconnected-(U2-MIC1N-Pad20)") (class "Default")
      (node (ref "U2") (pin "20") (pinfunction "MIC1N_20") (pintype "passive"))
    )
    (net (code "84") (name "unconnected-(U2-MIC1P-Pad19)") (class "Default")
      (node (ref "U2") (pin "19") (pinfunction "MIC1P_19") (pintype "passive"))
    )
    (net (code "85") (name "unconnected-(U2-PCM_CLK-Pad46)") (class "Default")
      (node (ref "U2") (pin "46") (pinfunction "PCM_CLK_46") (pintype "passive"))
    )
    (net (code "86") (name "unconnected-(U2-PCM_IN-Pad47)") (class "Default")
      (node (ref "U2") (pin "47") (pinfunction "PCM_IN_47") (pintype "passive"))
    )
    (net (code "87") (name "unconnected-(U2-PCM_OUT-Pad48)") (class "Default")
      (node (ref "U2") (pin "48") (pinfunction "PCM_OUT_48") (pintype "passive"))
    )
    (net (code "88") (name "unconnected-(U2-PCM_SYNC-Pad45)") (class "Default")
      (node (ref "U2") (pin "45") (pinfunction "PCM_SYNC_45") (pintype "passive"))
    )
    (net (code "89") (name "unconnected-(U2-PWM1-Pad42)") (class "Default")
      (node (ref "U2") (pin "42") (pinfunction "PWM1_42") (pintype "passive"))
    )
    (net (code "90") (name "unconnected-(U2-PWM2-Pad41)") (class "Default")
      (node (ref "U2") (pin "41") (pinfunction "PWM2_41") (pintype "passive"))
    )
    (net (code "91") (name "unconnected-(U2-RF_SYNC-Pad63)") (class "Default")
      (node (ref "U2") (pin "63") (pinfunction "RF_SYNC_63") (pintype "passive"))
    )
    (net (code "92") (name "unconnected-(U2-RI-Pad10)") (class "Default")
      (node (ref "U2") (pin "10") (pinfunction "RI_10") (pintype "passive"))
    )
    (net (code "93") (name "unconnected-(U2-ROW0-Pad58)") (class "Default")
      (node (ref "U2") (pin "58") (pinfunction "ROW0_58") (pintype "passive"))
    )
    (net (code "94") (name "unconnected-(U2-ROW1-Pad57)") (class "Default")
      (node (ref "U2") (pin "57") (pinfunction "ROW1_57") (pintype "passive"))
    )
    (net (code "95") (name "unconnected-(U2-ROW2-Pad56)") (class "Default")
      (node (ref "U2") (pin "56") (pinfunction "ROW2_56") (pintype "passive"))
    )
    (net (code "96") (name "unconnected-(U2-ROW3-Pad55)") (class "Default")
      (node (ref "U2") (pin "55") (pinfunction "ROW3_55") (pintype "passive"))
    )
    (net (code "97") (name "unconnected-(U2-RTS-Pad13)") (class "Default")
      (node (ref "U2") (pin "13") (pinfunction "RTS_13") (pintype "passive"))
    )
    (net (code "98") (name "unconnected-(U2-SCL-Pad39)") (class "Default")
      (node (ref "U2") (pin "39") (pinfunction "SCL_39") (pintype "passive"))
    )
    (net (code "99") (name "unconnected-(U2-SDA-Pad38)") (class "Default")
      (node (ref "U2") (pin "38") (pinfunction "SDA_38") (pintype "passive"))
    )
    (net (code "100") (name "unconnected-(U2-SIM_PRESENCE-Pad33)") (class "Default")
      (node (ref "U2") (pin "33") (pinfunction "SIM_PRESENCE_33") (pintype "passive"))
    )
    (net (code "101") (name "unconnected-(U2-SPK1N-Pad22)") (class "Default")
      (node (ref "U2") (pin "22") (pinfunction "SPK1N_22") (pintype "passive"))
    )
    (net (code "102") (name "unconnected-(U2-SPK1P-Pad21)") (class "Default")
      (node (ref "U2") (pin "21") (pinfunction "SPK1P_21") (pintype "passive"))
    )
    (net (code "103") (name "unconnected-(U2-STATUS-Pad49)") (class "Default")
      (node (ref "U2") (pin "49") (pinfunction "STATUS_49") (pintype "passive"))
    )
    (net (code "104") (name "unconnected-(U2-USB_DM-Pad27)") (class "Default")
      (node (ref "U2") (pin "27") (pinfunction "USB_DM_27") (pintype "passive"))
    )
    (net (code "105") (name "unconnected-(U2-USB_DP-Pad26)") (class "Default")
      (node (ref "U2") (pin "26") (pinfunction "USB_DP_26") (pintype "passive"))
    )
    (net (code "106") (name "unconnected-(U2-VBUS-Pad25)") (class "Default")
      (node (ref "U2") (pin "25") (pinfunction "VBUS_25") (pintype "passive"))
    )
    (net (code "107") (name "unconnected-(U2-VDD_EXT-Pad7)") (class "Default")
      (node (ref "U2") (pin "7") (pinfunction "VDD_EXT_7") (pintype "passive"))
    )
    (net (code "108") (name "unconnected-(U2-~{RESET}-Pad16)") (class "Default")
      (node (ref "U2") (pin "16") (pinfunction "~{RESET}_16") (pintype "passive"))
    )
    (net (code "109") (name "unconnected-(U3-(MISO)_PB4-Pad16)") (class "Default")
      (node (ref "U3") (pin "16") (pinfunction "(MISO)_PB4_16") (pintype "passive"))
    )
    (net (code "110") (name "unconnected-(U3-(MOSI)_PB3-Pad15)") (class "Default")
      (node (ref "U3") (pin "15") (pinfunction "(MOSI)_PB3_15") (pintype "passive"))
    )
    (net (code "111") (name "unconnected-(U3-(XCK)_PD4-Pad2)") (class "Default")
      (node (ref "U3") (pin "2") (pinfunction "(XCK)_PD4_2") (pintype "passive"))
    )
    (net (code "112") (name "unconnected-(U3-(XTAL1)_PB6-Pad7)") (class "Default")
      (node (ref "U3") (pin "7") (pinfunction "(XTAL1)_PB6_7") (pintype "passive"))
    )
    (net (code "113") (name "unconnected-(U3-(XTAL2)_PB7-Pad8)") (class "Default")
      (node (ref "U3") (pin "8") (pinfunction "(XTAL2)_PB7_8") (pintype "passive"))
    )
    (net (code "114") (name "unconnected-(U3-ADC6-Pad19)") (class "Default")
      (node (ref "U3") (pin "19") (pinfunction "ADC6_19") (pintype "passive"))
    )
    (net (code "115") (name "unconnected-(U3-ADC7-Pad22)") (class "Default")
      (node (ref "U3") (pin "22") (pinfunction "ADC7_22") (pintype "passive"))
    )
    (net (code "116") (name "unconnected-(U3-AREF-Pad20)") (class "Default")
      (node (ref "U3") (pin "20") (pinfunction "AREF_20") (pintype "passive"))
    )
    (net (code "117") (name "unconnected-(U3-AVCC-Pad18)") (class "Default")
      (node (ref "U3") (pin "18") (pinfunction "AVCC_18") (pintype "passive"))
    )
    (net (code "118") (name "unconnected-(U3-GND-Pad3)") (class "Default")
      (node (ref "U3") (pin "3") (pinfunction "GND_3") (pintype "passive"))
    )
    (net (code "119") (name "unconnected-(U3-GND-Pad5)") (class "Default")
      (node (ref "U3") (pin "5") (pinfunction "GND_5") (pintype "passive"))
    )
    (net (code "120") (name "unconnected-(U3-GND-Pad21)") (class "Default")
      (node (ref "U3") (pin "21") (pinfunction "GND_21") (pintype "passive"))
    )
    (net (code "121") (name "unconnected-(U3-PB0-Pad12)") (class "Default")
      (node (ref "U3") (pin "12") (pinfunction "PB0_12") (pintype "passive"))
    )
    (net (code "122") (name "unconnected-(U3-PB1-Pad13)") (class "Default")
      (node (ref "U3") (pin "13") (pinfunction "PB1_13") (pintype "passive"))
    )
    (net (code "123") (name "unconnected-(U3-PB2-Pad14)") (class "Default")
      (node (ref "U3") (pin "14") (pinfunction "PB2_14") (pintype "passive"))
    )
    (net (code "124") (name "unconnected-(U3-PB5_(SCK)-Pad17)") (class "Default")
      (node (ref "U3") (pin "17") (pinfunction "PB5_(SCK)_17") (pintype "passive"))
    )
    (net (code "125") (name "unconnected-(U3-PC0_(ADC0)-Pad23)") (class "Default")
      (node (ref "U3") (pin "23") (pinfunction "PC0_(ADC0)_23") (pintype "passive"))
    )
    (net (code "126") (name "unconnected-(U3-PC1_(ADC1)-Pad24)") (class "Default")
      (node (ref "U3") (pin "24") (pinfunction "PC1_(ADC1)_24") (pintype "passive"))
    )
    (net (code "127") (name "unconnected-(U3-PC2_(ADC2)-Pad25)") (class "Default")
      (node (ref "U3") (pin "25") (pinfunction "PC2_(ADC2)_25") (pintype "passive"))
    )
    (net (code "128") (name "unconnected-(U3-PC3_(ADC3)-Pad26)") (class "Default")
      (node (ref "U3") (pin "26") (pinfunction "PC3_(ADC3)_26") (pintype "passive"))
    )
    (net (code "129") (name "unconnected-(U3-PC4_(ADC4{slash}SDA)-Pad27)") (class "Default")
      (node (ref "U3") (pin "27") (pinfunction "PC4_(ADC4/SDA)_27") (pintype "passive"))
    )
    (net (code "130") (name "unconnected-(U3-PC5_(ADC5{slash}SCL)-Pad28)") (class "Default")
      (node (ref "U3") (pin "28") (pinfunction "PC5_(ADC5/SCL)_28") (pintype "passive"))
    )
    (net (code "131") (name "unconnected-(U3-PC6_(RESET)-Pad29)") (class "Default")
      (node (ref "U3") (pin "29") (pinfunction "PC6_(RESET)_29") (pintype "passive"))
    )
    (net (code "132") (name "unconnected-(U3-PD0_(RXD)-Pad30)") (class "Default")
      (node (ref "U3") (pin "30") (pinfunction "PD0_(RXD)_30") (pintype "passive"))
    )
    (net (code "133") (name "unconnected-(U3-PD1_(TXD)-Pad31)") (class "Default")
      (node (ref "U3") (pin "31") (pinfunction "PD1_(TXD)_31") (pintype "passive"))
    )
    (net (code "134") (name "unconnected-(U3-PD2-Pad32)") (class "Default")
      (node (ref "U3") (pin "32") (pinfunction "PD2_32") (pintype "passive"))
    )
    (net (code "135") (name "unconnected-(U3-PD3-Pad1)") (class "Default")
      (node (ref "U3") (pin "1") (pinfunction "PD3_1") (pintype "passive"))
    )
    (net (code "136") (name "unconnected-(U3-PD5-Pad9)") (class "Default")
      (node (ref "U3") (pin "9") (pinfunction "PD5_9") (pintype "passive"))
    )
    (net (code "137") (name "unconnected-(U3-PD6-Pad10)") (class "Default")
      (node (ref "U3") (pin "10") (pinfunction "PD6_10") (pintype "passive"))
    )
    (net (code "138") (name "unconnected-(U3-PD7-Pad11)") (class "Default")
      (node (ref "U3") (pin "11") (pinfunction "PD7_11") (pintype "passive"))
    )
    (net (code "139") (name "unconnected-(U3-VCC-Pad4)") (class "Default")
      (node (ref "U3") (pin "4") (pinfunction "VCC_4") (pintype "passive"))
    )
    (net (code "140") (name "unconnected-(U3-VCC-Pad6)") (class "Default")
      (node (ref "U3") (pin "6") (pinfunction "VCC_6") (pintype "passive"))
    )
    (net (code "141") (name "unconnected-(U4-GND-Pad4)") (class "Default")
      (node (ref "U4") (pin "4") (pinfunction "GND_4") (pintype "passive"))
    )
    (net (code "142") (name "unconnected-(U4-Invert_InputA-Pad2)") (class "Default")
      (node (ref "U4") (pin "2") (pinfunction "Invert_InputA_2") (pintype "passive"))
    )
    (net (code "143") (name "unconnected-(U4-Invert_InputB-Pad6)") (class "Default")
      (node (ref "U4") (pin "6") (pinfunction "Invert_InputB_6") (pintype "passive"))
    )
    (net (code "144") (name "unconnected-(U4-Non_invert_inputA-Pad3)") (class "Default")
      (node (ref "U4") (pin "3") (pinfunction "Non_invert_inputA_3") (pintype "passive"))
    )
    (net (code "145") (name "unconnected-(U4-Non_invert_inputB-Pad5)") (class "Default")
      (node (ref "U4") (pin "5") (pinfunction "Non_invert_inputB_5") (pintype "passive"))
    )
    (net (code "146") (name "unconnected-(U4-OutputA-Pad1)") (class "Default")
      (node (ref "U4") (pin "1") (pinfunction "OutputA_1") (pintype "passive"))
    )
    (net (code "147") (name "unconnected-(U4-OutputB-Pad7)") (class "Default")
      (node (ref "U4") (pin "7") (pinfunction "OutputB_7") (pintype "passive"))
    )
    (net (code "148") (name "unconnected-(U4-VCC-Pad8)") (class "Default")
      (node (ref "U4") (pin "8") (pinfunction "VCC_8") (pintype "passive"))
    )
    (net (code "149") (name "unconnected-(U5-Pad4)") (class "Default")
      (node (ref "U5") (pin "4") (pinfunction "4_4") (pintype "passive"))
    )
  )
)
